# H01R0_Backend.net
KiCad netlist of a schematic drawn in Altium Designer
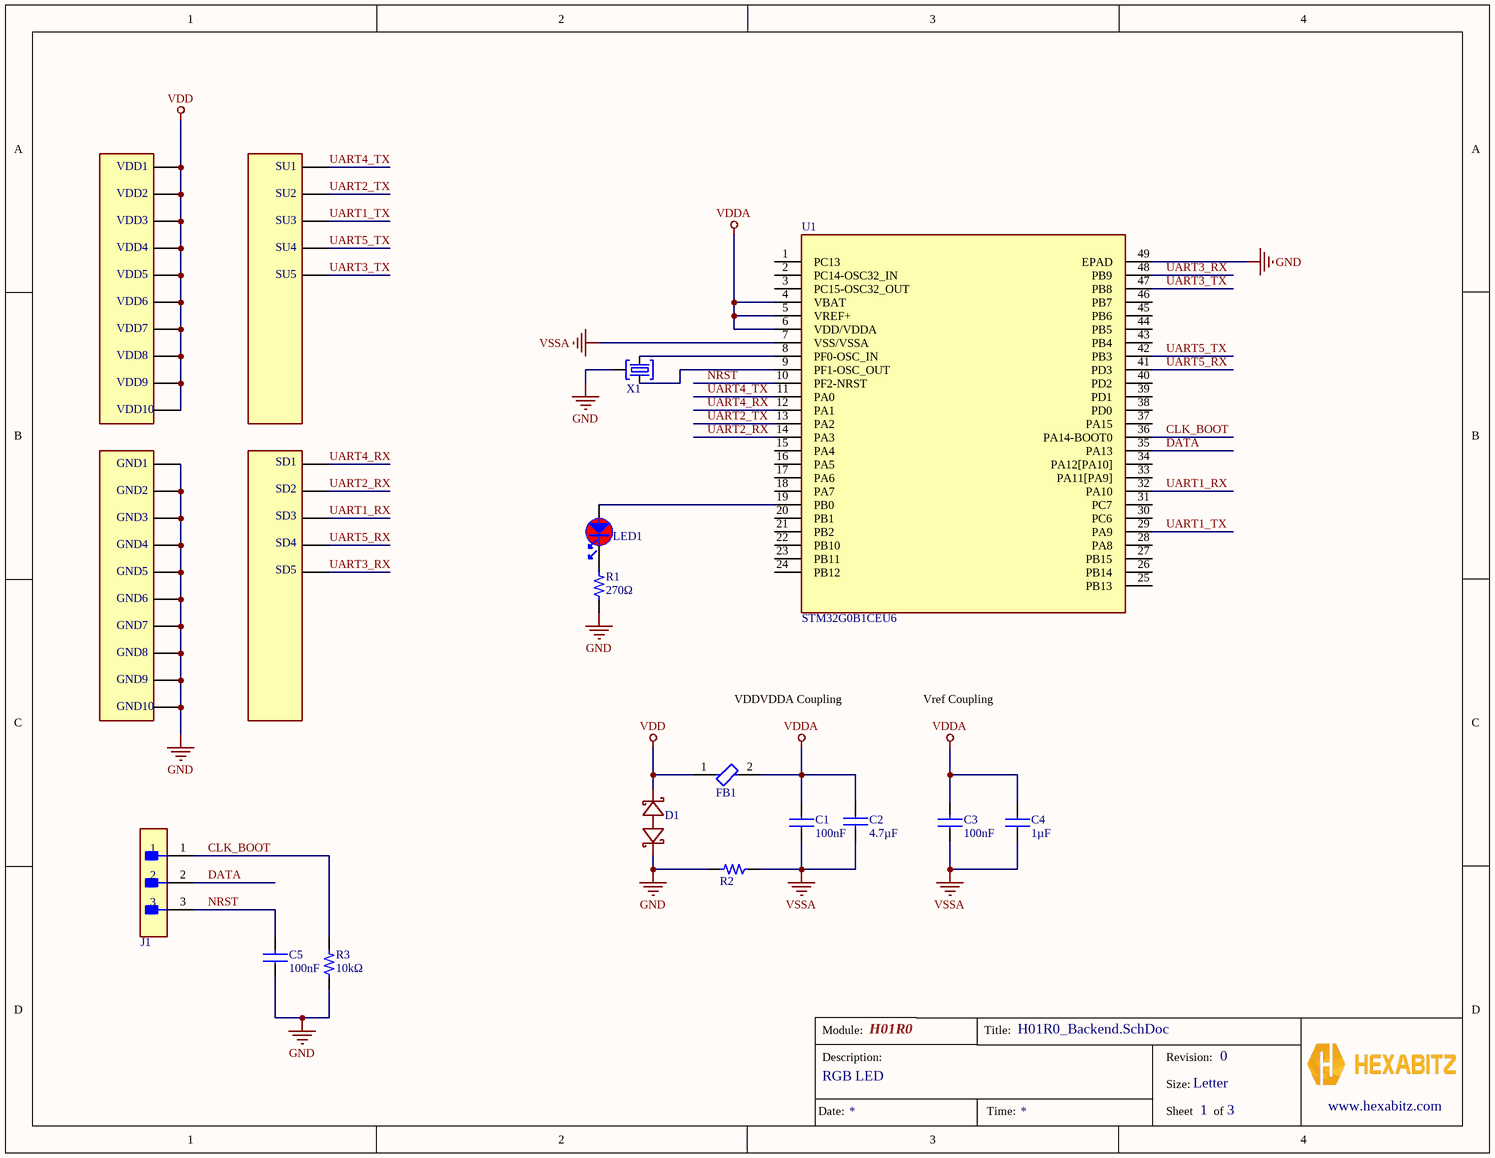
[diagram p0: H01R0_Backend.SchDoc]

(export (version "E")
  (design (tool "Eeschema 10.0.6"))
  (components
    (comp (ref "C1")
      (value "100nF")
      (footprint "C0603")
      (fields
        (field (name "MANUFACTURER") "Samsung Electro-Mechanics")
        (field (name "MANUFACTURER PART NUMBER") "CL10B104KA8NNNC")
        (field (name "TOLERANCE") "10%")
      )
      (libsource (lib "Hexabitz Altium Library") (part "generic Capacitor"))
    )
    (comp (ref "C2")
      (value "4.7µF")
      (footprint "C0805")
      (fields
        (field (name "MANUFACTURER") "Samsung Electro-Mechanics")
        (field (name "MANUFACTURER PART NUMBER") "CL21X475KAQNNNE")
        (field (name "TOLERANCE") "10%")
      )
      (libsource (lib "Hexabitz Altium Library") (part "generic Capacitor"))
    )
    (comp (ref "C3")
      (value "100nF")
      (footprint "C0603")
      (fields
        (field (name "MANUFACTURER") "Samsung Electro-Mechanics")
        (field (name "MANUFACTURER PART NUMBER") "CL10B104KA8NNNC")
        (field (name "TOLERANCE") "10%")
      )
      (libsource (lib "Hexabitz Altium Library") (part "generic Capacitor"))
    )
    (comp (ref "C4")
      (value "1µF")
      (footprint "C0805")
      (description "Ceramic Capacitor, Ceramic, 16V, 10% +Tol, 10% -Tol, X7R, 15% TC, 1uF, Surface Mount, 0805")
      (fields
        (field (name "MANUFACTURER") "Yageo Group")
        (field (name "MANUFACTURER PART NUMBER") "CC0805KKX7R7BB105")
      )
      (libsource (lib "Hexabitz Altium Library") (part "generic Capacitor"))
    )
    (comp (ref "C5")
      (value "100nF")
      (footprint "C0603")
      (fields
        (field (name "MANUFACTURER") "Samsung Electro-Mechanics")
        (field (name "MANUFACTURER PART NUMBER") "CL10B104KA8NNNC")
        (field (name "TOLERANCE") "10%")
      )
      (libsource (lib "Hexabitz Altium Library") (part "generic Capacitor"))
    )
    (comp (ref "D1")
      (value "CDSOD323-T03SC")
      (footprint "SOD2513X114N")
      (description "A 3V, 350W, bi-directional, standard capacitance, SOD323 pkg TVS Diode ¦ Bourns CDSOD323-T03SC")
      (fields (field (name "MANUFACTURER") "Bourns"))
      (libsource (lib "Hexabitz Altium Library") (part "CDSOD323-T03SC"))
    )
    (comp (ref "FB1")
      (value "MMZ1608Y300B")
      (footprint "FP-MMZ1608-0_8-MFG")
      (description "Ferrite Beads 0603 30ohms 1500mA Signal Line AEC-Q200")
      (fields
        (field (name "MANUFACTURER") "TDK")
        (field (name "MANUFACTURER PART NUMBER") "MMZ1608Y300BTD25")
      )
      (libsource (lib "Hexabitz Altium Library") (part "MMZ1608Y300B"))
    )
    (comp (ref "GND1")
      (value "HEXABIT_UART_PORT")
      (footprint "HEXABIT_POWER_PORT_D")
      (libsource (lib "hexabitz_connectors.Library") (part "HEXABIT_POWER_PORT_D"))
    )
    (comp (ref "GND2")
      (value "HEXABIT_UART_PORT")
      (footprint "HEXABIT_POWER_PORT_D")
      (libsource (lib "hexabitz_connectors.Library") (part "HEXABIT_POWER_PORT_D"))
    )
    (comp (ref "GND3")
      (value "HEXABIT_UART_PORT")
      (footprint "HEXABIT_POWER_PORT_D_300R")
      (libsource (lib "hexabitz_connectors.Library") (part "HEXABIT_POWER_PORT_D_300R"))
    )
    (comp (ref "GND4")
      (value "HEXABIT_UART_PORT")
      (footprint "HEXABIT_POWER_PORT_D")
      (libsource (lib "hexabitz_connectors.Library") (part "HEXABIT_POWER_PORT_D"))
    )
    (comp (ref "GND5")
      (value "HEXABIT_UART_PORT")
      (footprint "HEXABIT_POWER_PORT_D")
      (libsource (lib "hexabitz_connectors.Library") (part "HEXABIT_POWER_PORT_D"))
    )
    (comp (ref "GND6")
      (value "HEXABIT_UART_PORT")
      (footprint "HEXABIT_POWER_PORT_D")
      (libsource (lib "hexabitz_connectors.Library") (part "HEXABIT_POWER_PORT_D"))
    )
    (comp (ref "GND7")
      (value "HEXABIT_UART_PORT")
      (footprint "HEXABIT_POWER_PORT_D")
      (libsource (lib "hexabitz_connectors.Library") (part "HEXABIT_POWER_PORT_D"))
    )
    (comp (ref "GND8")
      (value "HEXABIT_UART_PORT")
      (footprint "HEXABIT_POWER_PORT_D_300L")
      (libsource (lib "hexabitz_connectors.Library") (part "HEXABIT_POWER_PORT_D_300L"))
    )
    (comp (ref "GND9")
      (value "HEXABIT_UART_PORT")
      (footprint "HEXABIT_POWER_PORT_D")
      (libsource (lib "hexabitz_connectors.Library") (part "HEXABIT_POWER_PORT_D"))
    )
    (comp (ref "GND10")
      (value "HEXABIT_UART_PORT")
      (footprint "HEXABIT_POWER_PORT_D")
      (libsource (lib "hexabitz_connectors.Library") (part "HEXABIT_POWER_PORT_D"))
    )
    (comp (ref "J1")
      (value "TSW-103-14-G-S")
      (footprint "FP-TSW-103-14-G-S-MFG")
      (description "CONN HEADER VERT 3POS 2.54MM")
      (libsource (lib "Altium Content Vault") (part "cd3439d6ef35ae5d9b27ec4fdd3e828"))
    )
    (comp (ref "LED1")
      (value "VLMS1300-GS08")
      (footprint "FP-6_541-5092_01-4-MFG")
      (description "LED Uni-Color Super Red 639nm 2-Pin Chip 0603(1608Metric) T/R")
      (fields (field (name "MANUFACTURER") "Vishay Semiconductors"))
      (libsource (lib "Hexabitz Altium Library") (part "VLMS1300-GS08"))
    )
    (comp (ref "R1")
      (value "270Ω")
      (footprint "R0603")
      (description "Res Thick Film 0603 270 Ohm 5% 0.1W(1/10W) ±200ppm/C Pad SMD Automotive T/R")
      (fields
        (field (name "MANUFACTURER") "Panasonic")
        (field (name "MANUFACTURER PART NUMBER") "ERJ-3GEYJ271V")
      )
      (libsource (lib "") (part "generic Resistor_2"))
    )
    (comp (ref "R2")
      (value "Manufacturer Part Number")
      (footprint "R0603")
      (libsource (lib "Hexabitz Altium Library") (part "generic Resistor"))
    )
    (comp (ref "R3")
      (value "10kΩ")
      (footprint "R0603")
      (description "100mW Thick Film Resistors ±100ppm/℃ ±1% 10kΩ 0603 Chip Resistor - Surface Mount ROHS")
      (fields
        (field (name "MANUFACTURER") "Yageo Group")
        (field (name "MANUFACTURER PART NUMBER") "RC0603FR-0710KL")
      )
      (libsource (lib "") (part "generic Resistor_1"))
    )
    (comp (ref "SD1")
      (value "HEXABIT_UART_PORT")
      (footprint "HEXABIT_UART_PORT_D")
      (libsource (lib "hexabitz_connectors.Library") (part "HEXABIT_UART_PORT_D"))
    )
    (comp (ref "SD2")
      (value "HEXABIT_UART_PORT")
      (footprint "HEXABIT_UART_PORT_D")
      (libsource (lib "hexabitz_connectors.Library") (part "HEXABIT_UART_PORT_D"))
    )
    (comp (ref "SD3")
      (value "HEXABIT_UART_PORT")
      (footprint "HEXABIT_UART_PORT_D")
      (libsource (lib "hexabitz_connectors.Library") (part "HEXABIT_UART_PORT_D"))
    )
    (comp (ref "SD4")
      (value "HEXABIT_UART_PORT")
      (footprint "HEXABIT_UART_PORT_D")
      (libsource (lib "hexabitz_connectors.Library") (part "HEXABIT_UART_PORT_D"))
    )
    (comp (ref "SD5")
      (value "HEXABIT_UART_PORT")
      (footprint "HEXABIT_UART_PORT_D")
      (libsource (lib "hexabitz_connectors.Library") (part "HEXABIT_UART_PORT_D"))
    )
    (comp (ref "SU1")
      (value "HEXABIT_UART_PORT")
      (footprint "HEXABIT_UART_PORT_U")
      (libsource (lib "hexabitz_connectors.Library") (part "HEXABIT_UART_PORT_U"))
    )
    (comp (ref "SU2")
      (value "HEXABIT_UART_PORT")
      (footprint "HEXABIT_UART_PORT_U")
      (libsource (lib "hexabitz_connectors.Library") (part "HEXABIT_UART_PORT_U"))
    )
    (comp (ref "SU3")
      (value "HEXABIT_UART_PORT")
      (footprint "HEXABIT_UART_PORT_U")
      (libsource (lib "hexabitz_connectors.Library") (part "HEXABIT_UART_PORT_U"))
    )
    (comp (ref "SU4")
      (value "HEXABIT_UART_PORT")
      (footprint "HEXABIT_UART_PORT_U")
      (libsource (lib "hexabitz_connectors.Library") (part "HEXABIT_UART_PORT_U"))
    )
    (comp (ref "SU5")
      (value "HEXABIT_UART_PORT")
      (footprint "HEXABIT_UART_PORT_U")
      (libsource (lib "hexabitz_connectors.Library") (part "HEXABIT_UART_PORT_U"))
    )
    (comp (ref "U1")
      (value "STM32G0B1CEU6")
      (footprint "QFN50P700X700X65-49N-D")
      (description "MCU 32-bit ARM Cortex M0+ RISC 512KB Flash 1.8V/2.5V/3.3V 48-Pin UFQFPN EP Tray")
      (fields
        (field (name "MANUFACTURER") "STMicroelectronics")
        (field (name "MANUFACTURER PART NUMBER") "STM32G0B1CEU6")
      )
      (libsource (lib "Hexabitz Altium Library") (part "STM32G0B1CEU6"))
    )
    (comp (ref "VDD1")
      (value "HEXABIT_UART_PORT")
      (footprint "HEXABIT_POWER_PORT_U")
      (libsource (lib "hexabitz_connectors.Library") (part "HEXABIT_POWER_PORT_U"))
    )
    (comp (ref "VDD2")
      (value "HEXABIT_UART_PORT")
      (footprint "HEXABIT_POWER_PORT_U")
      (libsource (lib "hexabitz_connectors.Library") (part "HEXABIT_POWER_PORT_U"))
    )
    (comp (ref "VDD3")
      (value "HEXABIT_UART_PORT")
      (footprint "HEXABIT_POWER_PORT_U_300R")
      (libsource (lib "hexabitz_connectors.Library") (part "HEXABIT_POWER_PORT_U_300R"))
    )
    (comp (ref "VDD4")
      (value "HEXABIT_UART_PORT")
      (footprint "HEXABIT_POWER_PORT_U")
      (libsource (lib "hexabitz_connectors.Library") (part "HEXABIT_POWER_PORT_U"))
    )
    (comp (ref "VDD5")
      (value "HEXABIT_UART_PORT")
      (footprint "HEXABIT_POWER_PORT_U")
      (libsource (lib "hexabitz_connectors.Library") (part "HEXABIT_POWER_PORT_U"))
    )
    (comp (ref "VDD6")
      (value "HEXABIT_UART_PORT")
      (footprint "HEXABIT_POWER_PORT_U")
      (libsource (lib "hexabitz_connectors.Library") (part "HEXABIT_POWER_PORT_U"))
    )
    (comp (ref "VDD7")
      (value "HEXABIT_UART_PORT")
      (footprint "HEXABIT_POWER_PORT_U")
      (libsource (lib "hexabitz_connectors.Library") (part "HEXABIT_POWER_PORT_U"))
    )
    (comp (ref "VDD8")
      (value "HEXABIT_UART_PORT")
      (footprint "HEXABIT_POWER_PORT_U_300L")
      (libsource (lib "hexabitz_connectors.Library") (part "HEXABIT_POWER_PORT_U_300L"))
    )
    (comp (ref "VDD9")
      (value "HEXABIT_UART_PORT")
      (footprint "HEXABIT_POWER_PORT_U")
      (libsource (lib "hexabitz_connectors.Library") (part "HEXABIT_POWER_PORT_U"))
    )
    (comp (ref "VDD10")
      (value "HEXABIT_UART_PORT")
      (footprint "HEXABIT_POWER_PORT_U")
      (libsource (lib "hexabitz_connectors.Library") (part "HEXABIT_POWER_PORT_U"))
    )
    (comp (ref "X1")
      (value "CSTCE8M00G52Z-R0")
      (footprint "XTALL_CSTCE8M00G52")
      (description "Ceramic Resonator 8MHz ±0.5% (Tol) ±0.2% (Stability) 10pF 40Ohm 3-Pin CSMD T/R")
      (fields (field (name "MANUFACTURER") "Murata") (field (name "TOLERANCE") "0.5%"))
      (libsource (lib "Hexabitz Altium Library") (part "CSTCE8M00G52Z-R0"))
    )
  )
  (nets
    (net (code "1") (name "/CLK_BOOT") (class "Default")
      (node (ref "J1") (pin "1") (pinfunction "1_1") (pintype "passive"))
      (node (ref "R3") (pin "1") (pinfunction "1_1") (pintype "passive"))
      (node (ref "U1") (pin "36") (pinfunction "PA14-BOOT0_36") (pintype "passive"))
    )
    (net (code "2") (name "/DATA") (class "Default")
      (node (ref "J1") (pin "2") (pinfunction "2_2") (pintype "passive"))
      (node (ref "U1") (pin "35") (pinfunction "PA13_35") (pintype "passive"))
    )
    (net (code "3") (name "/NRST") (class "Default")
      (node (ref "C5") (pin "2") (pinfunction "2_2") (pintype "passive"))
      (node (ref "J1") (pin "3") (pinfunction "3_3") (pintype "passive"))
      (node (ref "U1") (pin "10") (pinfunction "PF2-NRST_10") (pintype "passive"))
    )
    (net (code "4") (name "/UART1_RX") (class "Default")
      (node (ref "SD3") (pin "UART_D") (pinfunction "UART_D_UART_D") (pintype "passive"))
      (node (ref "U1") (pin "32") (pinfunction "PA10_32") (pintype "passive"))
    )
    (net (code "5") (name "/UART1_TX") (class "Default")
      (node (ref "SU3") (pin "UART_U") (pinfunction "UART_U_UART_U") (pintype "passive"))
      (node (ref "U1") (pin "29") (pinfunction "PA9_29") (pintype "passive"))
    )
    (net (code "6") (name "/UART2_RX") (class "Default")
      (node (ref "SD2") (pin "UART_D") (pinfunction "UART_D_UART_D") (pintype "passive"))
      (node (ref "U1") (pin "14") (pinfunction "PA3_14") (pintype "passive"))
    )
    (net (code "7") (name "/UART2_TX") (class "Default")
      (node (ref "SU2") (pin "UART_U") (pinfunction "UART_U_UART_U") (pintype "passive"))
      (node (ref "U1") (pin "13") (pinfunction "PA2_13") (pintype "passive"))
    )
    (net (code "8") (name "/UART3_RX") (class "Default")
      (node (ref "SD5") (pin "UART_D") (pinfunction "UART_D_UART_D") (pintype "passive"))
      (node (ref "U1") (pin "48") (pinfunction "PB9_48") (pintype "passive"))
    )
    (net (code "9") (name "/UART3_TX") (class "Default")
      (node (ref "SU5") (pin "UART_U") (pinfunction "UART_U_UART_U") (pintype "passive"))
      (node (ref "U1") (pin "47") (pinfunction "PB8_47") (pintype "passive"))
    )
    (net (code "10") (name "/UART4_RX") (class "Default")
      (node (ref "SD1") (pin "UART_D") (pinfunction "UART_D_UART_D") (pintype "passive"))
      (node (ref "U1") (pin "12") (pinfunction "PA1_12") (pintype "passive"))
    )
    (net (code "11") (name "/UART4_TX") (class "Default")
      (node (ref "SU1") (pin "UART_U") (pinfunction "UART_U_UART_U") (pintype "passive"))
      (node (ref "U1") (pin "11") (pinfunction "PA0_11") (pintype "passive"))
    )
    (net (code "12") (name "/UART5_RX") (class "Default")
      (node (ref "SD4") (pin "UART_D") (pinfunction "UART_D_UART_D") (pintype "passive"))
      (node (ref "U1") (pin "41") (pinfunction "PD3_41") (pintype "passive"))
    )
    (net (code "13") (name "/UART5_TX") (class "Default")
      (node (ref "SU4") (pin "UART_U") (pinfunction "UART_U_UART_U") (pintype "passive"))
      (node (ref "U1") (pin "42") (pinfunction "PB3_42") (pintype "passive"))
    )
    (net (code "14") (name "GND") (class "Default")
      (node (ref "C5") (pin "1") (pinfunction "1_1") (pintype "passive"))
      (node (ref "D1") (pin "1") (pinfunction "A_1") (pintype "passive"))
      (node (ref "GND1") (pin "Pwr_D") (pinfunction "Pwr_D_Pwr_D") (pintype "passive"))
      (node (ref "GND10") (pin "Pwr_D") (pinfunction "Pwr_D_Pwr_D") (pintype "passive"))
      (node (ref "GND2") (pin "Pwr_D") (pinfunction "Pwr_D_Pwr_D") (pintype "passive"))
      (node (ref "GND3") (pin "Pwr_D") (pinfunction "Pwr_D_Pwr_D") (pintype "passive"))
      (node (ref "GND4") (pin "Pwr_D") (pinfunction "Pwr_D_Pwr_D") (pintype "passive"))
      (node (ref "GND5") (pin "Pwr_D") (pinfunction "Pwr_D_Pwr_D") (pintype "passive"))
      (node (ref "GND6") (pin "Pwr_D") (pinfunction "Pwr_D_Pwr_D") (pintype "passive"))
      (node (ref "GND7") (pin "Pwr_D") (pinfunction "Pwr_D_Pwr_D") (pintype "passive"))
      (node (ref "GND8") (pin "Pwr_D") (pinfunction "Pwr_D_Pwr_D") (pintype "passive"))
      (node (ref "GND9") (pin "Pwr_D") (pinfunction "Pwr_D_Pwr_D") (pintype "passive"))
      (node (ref "R1") (pin "1") (pinfunction "1_1") (pintype "passive"))
      (node (ref "R2") (pin "1") (pinfunction "1_1") (pintype "passive"))
      (node (ref "R3") (pin "2") (pinfunction "2_2") (pintype "passive"))
      (node (ref "U1") (pin "49") (pinfunction "EPAD_49") (pintype "passive"))
      (node (ref "X1") (pin "P$2") (pinfunction "2_P$2") (pintype "passive"))
    )
    (net (code "15") (name "Net-(LED1-Pad1)") (class "Default")
      (node (ref "LED1") (pin "1") (pintype "passive"))
      (node (ref "R1") (pin "2") (pinfunction "2_2") (pintype "passive"))
    )
    (net (code "16") (name "Net-(U1-PB0)") (class "Default")
      (node (ref "LED1") (pin "2") (pintype "passive"))
      (node (ref "U1") (pin "19") (pinfunction "PB0_19") (pintype "passive"))
    )
    (net (code "17") (name "Net-(U1-PF0-OSC_IN)") (class "Default")
      (node (ref "U1") (pin "8") (pinfunction "PF0-OSC_IN_8") (pintype "passive"))
      (node (ref "X1") (pin "P$3") (pinfunction "3_P$3") (pintype "passive"))
    )
    (net (code "18") (name "Net-(U1-PF1-OSC_OUT)") (class "Default")
      (node (ref "U1") (pin "9") (pinfunction "PF1-OSC_OUT_9") (pintype "passive"))
      (node (ref "X1") (pin "P$1") (pinfunction "1_P$1") (pintype "passive"))
    )
    (net (code "19") (name "VDD") (class "Default")
      (node (ref "D1") (pin "2") (pinfunction "C_2") (pintype "passive"))
      (node (ref "FB1") (pin "1") (pinfunction "1_1") (pintype "passive"))
      (node (ref "VDD1") (pin "Pwr_U") (pinfunction "Pwr_U_Pwr_U") (pintype "passive"))
      (node (ref "VDD10") (pin "Pwr_U") (pinfunction "Pwr_U_Pwr_U") (pintype "passive"))
      (node (ref "VDD2") (pin "Pwr_U") (pinfunction "Pwr_U_Pwr_U") (pintype "passive"))
      (node (ref "VDD3") (pin "Pwr_U") (pinfunction "Pwr_U_Pwr_U") (pintype "passive"))
      (node (ref "VDD4") (pin "Pwr_U") (pinfunction "Pwr_U_Pwr_U") (pintype "passive"))
      (node (ref "VDD5") (pin "Pwr_U") (pinfunction "Pwr_U_Pwr_U") (pintype "passive"))
      (node (ref "VDD6") (pin "Pwr_U") (pinfunction "Pwr_U_Pwr_U") (pintype "passive"))
      (node (ref "VDD7") (pin "Pwr_U") (pinfunction "Pwr_U_Pwr_U") (pintype "passive"))
      (node (ref "VDD8") (pin "Pwr_U") (pinfunction "Pwr_U_Pwr_U") (pintype "passive"))
      (node (ref "VDD9") (pin "Pwr_U") (pinfunction "Pwr_U_Pwr_U") (pintype "passive"))
    )
    (net (code "20") (name "VDDA") (class "Default")
      (node (ref "C1") (pin "2") (pinfunction "2_2") (pintype "passive"))
      (node (ref "C2") (pin "1") (pinfunction "1_1") (pintype "passive"))
      (node (ref "C3") (pin "2") (pinfunction "2_2") (pintype "passive"))
      (node (ref "C4") (pin "2") (pinfunction "2_2") (pintype "passive"))
      (node (ref "FB1") (pin "2") (pinfunction "2_2") (pintype "passive"))
      (node (ref "U1") (pin "4") (pinfunction "VBAT_4") (pintype "passive"))
      (node (ref "U1") (pin "5") (pinfunction "VREF+_5") (pintype "passive"))
      (node (ref "U1") (pin "6") (pinfunction "VDD/VDDA_6") (pintype "passive"))
    )
    (net (code "21") (name "VSSA") (class "Default")
      (node (ref "C1") (pin "1") (pinfunction "1_1") (pintype "passive"))
      (node (ref "C2") (pin "2") (pinfunction "2_2") (pintype "passive"))
      (node (ref "C3") (pin "1") (pinfunction "1_1") (pintype "passive"))
      (node (ref "C4") (pin "1") (pinfunction "1_1") (pintype "passive"))
      (node (ref "R2") (pin "2") (pinfunction "2_2") (pintype "passive"))
      (node (ref "U1") (pin "7") (pinfunction "VSS/VSSA_7") (pintype "passive"))
    )
    (net (code "22") (name "unconnected-(U1-PA4-Pad15)") (class "Default")
      (node (ref "U1") (pin "15") (pinfunction "PA4_15") (pintype "passive"))
    )
    (net (code "23") (name "unconnected-(U1-PA5-Pad16)") (class "Default")
      (node (ref "U1") (pin "16") (pinfunction "PA5_16") (pintype "passive"))
    )
    (net (code "24") (name "unconnected-(U1-PA6-Pad17)") (class "Default")
      (node (ref "U1") (pin "17") (pinfunction "PA6_17") (pintype "passive"))
    )
    (net (code "25") (name "unconnected-(U1-PA7-Pad18)") (class "Default")
      (node (ref "U1") (pin "18") (pinfunction "PA7_18") (pintype "passive"))
    )
    (net (code "26") (name "unconnected-(U1-PA8-Pad28)") (class "Default")
      (node (ref "U1") (pin "28") (pinfunction "PA8_28") (pintype "passive"))
    )
    (net (code "27") (name "unconnected-(U1-PA11[PA9]-Pad33)") (class "Default")
      (node (ref "U1") (pin "33") (pinfunction "PA11[PA9]_33") (pintype "passive"))
    )
    (net (code "28") (name "unconnected-(U1-PA12[PA10]-Pad34)") (class "Default")
      (node (ref "U1") (pin "34") (pinfunction "PA12[PA10]_34") (pintype "passive"))
    )
    (net (code "29") (name "unconnected-(U1-PA15-Pad37)") (class "Default")
      (node (ref "U1") (pin "37") (pinfunction "PA15_37") (pintype "passive"))
    )
    (net (code "30") (name "unconnected-(U1-PB1-Pad20)") (class "Default")
      (node (ref "U1") (pin "20") (pinfunction "PB1_20") (pintype "passive"))
    )
    (net (code "31") (name "unconnected-(U1-PB2-Pad21)") (class "Default")
      (node (ref "U1") (pin "21") (pinfunction "PB2_21") (pintype "passive"))
    )
    (net (code "32") (name "unconnected-(U1-PB4-Pad43)") (class "Default")
      (node (ref "U1") (pin "43") (pinfunction "PB4_43") (pintype "passive"))
    )
    (net (code "33") (name "unconnected-(U1-PB5-Pad44)") (class "Default")
      (node (ref "U1") (pin "44") (pinfunction "PB5_44") (pintype "passive"))
    )
    (net (code "34") (name "unconnected-(U1-PB6-Pad45)") (class "Default")
      (node (ref "U1") (pin "45") (pinfunction "PB6_45") (pintype "passive"))
    )
    (net (code "35") (name "unconnected-(U1-PB7-Pad46)") (class "Default")
      (node (ref "U1") (pin "46") (pinfunction "PB7_46") (pintype "passive"))
    )
    (net (code "36") (name "unconnected-(U1-PB10-Pad22)") (class "Default")
      (node (ref "U1") (pin "22") (pinfunction "PB10_22") (pintype "passive"))
    )
    (net (code "37") (name "unconnected-(U1-PB11-Pad23)") (class "Default")
      (node (ref "U1") (pin "23") (pinfunction "PB11_23") (pintype "passive"))
    )
    (net (code "38") (name "unconnected-(U1-PB12-Pad24)") (class "Default")
      (node (ref "U1") (pin "24") (pinfunction "PB12_24") (pintype "passive"))
    )
    (net (code "39") (name "unconnected-(U1-PB13-Pad25)") (class "Default")
      (node (ref "U1") (pin "25") (pinfunction "PB13_25") (pintype "passive"))
    )
    (net (code "40") (name "unconnected-(U1-PB14-Pad26)") (class "Default")
      (node (ref "U1") (pin "26") (pinfunction "PB14_26") (pintype "passive"))
    )
    (net (code "41") (name "unconnected-(U1-PB15-Pad27)") (class "Default")
      (node (ref "U1") (pin "27") (pinfunction "PB15_27") (pintype "passive"))
    )
    (net (code "42") (name "unconnected-(U1-PC6-Pad30)") (class "Default")
      (node (ref "U1") (pin "30") (pinfunction "PC6_30") (pintype "passive"))
    )
    (net (code "43") (name "unconnected-(U1-PC7-Pad31)") (class "Default")
      (node (ref "U1") (pin "31") (pinfunction "PC7_31") (pintype "passive"))
    )
    (net (code "44") (name "unconnected-(U1-PC13-Pad1)") (class "Default")
      (node (ref "U1") (pin "1") (pinfunction "PC13_1") (pintype "passive"))
    )
    (net (code "45") (name "unconnected-(U1-PC14-OSC32_IN-Pad2)") (class "Default")
      (node (ref "U1") (pin "2") (pinfunction "PC14-OSC32_IN_2") (pintype "passive"))
    )
    (net (code "46") (name "unconnected-(U1-PC15-OSC32_OUT-Pad3)") (class "Default")
      (node (ref "U1") (pin "3") (pinfunction "PC15-OSC32_OUT_3") (pintype "passive"))
    )
    (net (code "47") (name "unconnected-(U1-PD0-Pad38)") (class "Default")
      (node (ref "U1") (pin "38") (pinfunction "PD0_38") (pintype "passive"))
    )
    (net (code "48") (name "unconnected-(U1-PD1-Pad39)") (class "Default")
      (node (ref "U1") (pin "39") (pinfunction "PD1_39") (pintype "passive"))
    )
    (net (code "49") (name "unconnected-(U1-PD2-Pad40)") (class "Default")
      (node (ref "U1") (pin "40") (pinfunction "PD2_40") (pintype "passive"))
    )
  )
)
